# Dual_Motor_Driver.net
KiCad netlist of a schematic drawn in EAGLE
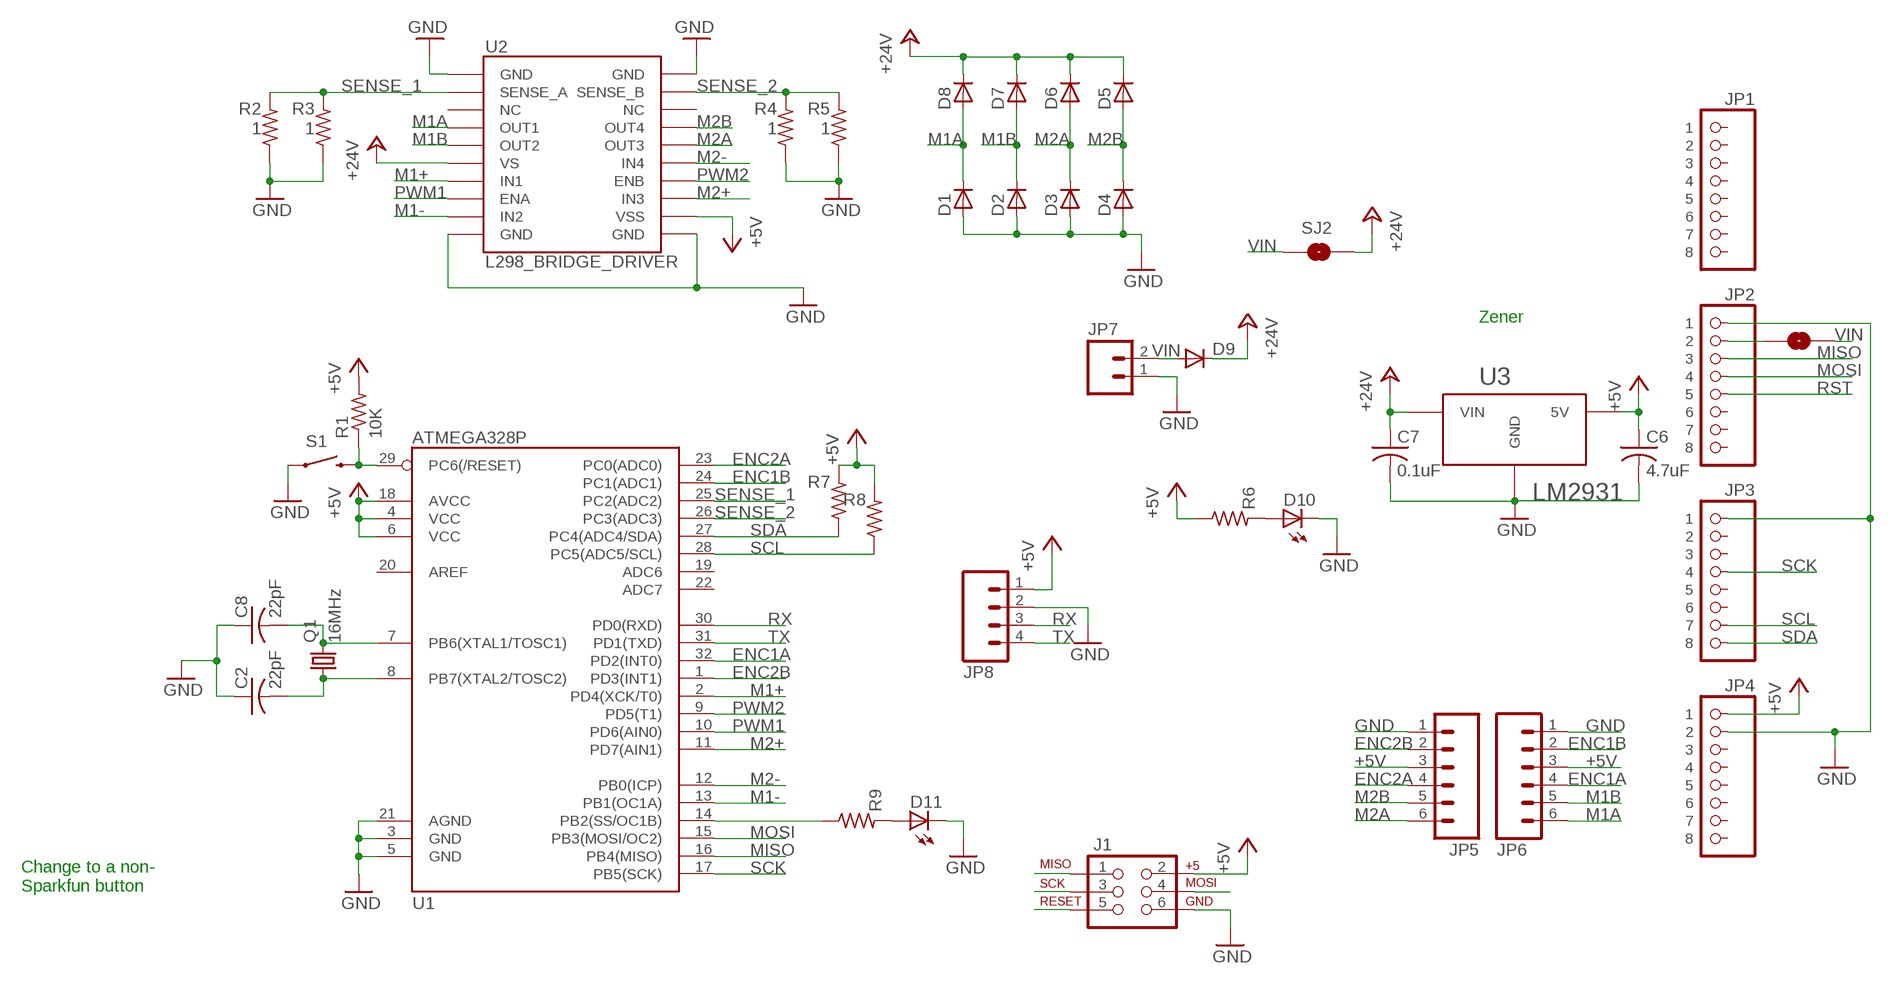
[diagram p0: schematic, sheet 1]

(export (version "E")
  (design (tool "Eeschema 10.0.6"))
  (components
    (comp (ref "C2")
      (value "22pF")
      (footprint "eagle-import:C0603")
      (libsource (lib "eagle-import") (part "C-USC0603"))
    )
    (comp (ref "C6")
      (value "4.7uF")
      (footprint "eagle-import:C0603")
      (libsource (lib "eagle-import") (part "C-USC0603"))
    )
    (comp (ref "C7")
      (value "0.1uF")
      (footprint "eagle-import:C0603")
      (libsource (lib "eagle-import") (part "C-USC0603"))
    )
    (comp (ref "C8")
      (value "22pF")
      (footprint "eagle-import:C0603")
      (libsource (lib "eagle-import") (part "C-USC0603"))
    )
    (comp (ref "D1")
      (value "D-SOD123")
      (footprint "eagle-import:SOD123")
      (fields (field (name "PART#") "CDBW140-G"))
      (libsource (lib "eagle-import") (part "D-SOD123"))
    )
    (comp (ref "D2")
      (value "D-SOD123")
      (footprint "eagle-import:SOD123")
      (fields (field (name "PART#") "CDBW140-G"))
      (libsource (lib "eagle-import") (part "D-SOD123"))
    )
    (comp (ref "D3")
      (value "D-SOD123")
      (footprint "eagle-import:SOD123")
      (fields (field (name "PART#") "CDBW140-G"))
      (libsource (lib "eagle-import") (part "D-SOD123"))
    )
    (comp (ref "D4")
      (value "D-SOD123")
      (footprint "eagle-import:SOD123")
      (fields (field (name "PART#") "CDBW140-G"))
      (libsource (lib "eagle-import") (part "D-SOD123"))
    )
    (comp (ref "D5")
      (value "D-SOD123")
      (footprint "eagle-import:SOD123")
      (fields (field (name "PART#") "CDBW140-G"))
      (libsource (lib "eagle-import") (part "D-SOD123"))
    )
    (comp (ref "D6")
      (value "D-SOD123")
      (footprint "eagle-import:SOD123")
      (fields (field (name "PART#") "CDBW140-G"))
      (libsource (lib "eagle-import") (part "D-SOD123"))
    )
    (comp (ref "D7")
      (value "D-SOD123")
      (footprint "eagle-import:SOD123")
      (fields (field (name "PART#") "CDBW140-G"))
      (libsource (lib "eagle-import") (part "D-SOD123"))
    )
    (comp (ref "D8")
      (value "D-SOD123")
      (footprint "eagle-import:SOD123")
      (fields (field (name "PART#") "CDBW140-G"))
      (libsource (lib "eagle-import") (part "D-SOD123"))
    )
    (comp (ref "D9")
      (value "DIODESMB")
      (footprint "eagle-import:SMB-DIODE")
      (libsource (lib "eagle-import") (part "DIODESMB"))
    )
    (comp (ref "D10")
      (value "LED-GREENLED-0805_NO_SILK")
      (footprint "eagle-import:LED-0805")
      (libsource (lib "eagle-import") (part "LED-GREENLED-0805_NO_SILK"))
    )
    (comp (ref "D11")
      (value "LED-GREENLED-0805_NO_SILK")
      (footprint "eagle-import:LED-0805")
      (libsource (lib "eagle-import") (part "LED-GREENLED-0805_NO_SILK"))
    )
    (comp (ref "J1")
      (value "AVR_SPI_PRG_62X3_LOCK")
      (footprint "eagle-import:2X3_LOCK")
      (libsource (lib "eagle-import") (part "AVR_SPI_PRG_62X3_LOCK"))
    )
    (comp (ref "JP1")
      (value "8-PIN_HEADER")
      (footprint "eagle-import:8-PIN_RECEPTACLE_LOCK_NO-SS")
      (libsource (lib "eagle-import") (part "8-PIN_HEADER"))
    )
    (comp (ref "JP2")
      (value "8-PIN_HEADER")
      (footprint "eagle-import:8-PIN_RECEPTACLE_LOCK_NO-SS")
      (libsource (lib "eagle-import") (part "8-PIN_HEADER"))
    )
    (comp (ref "JP3")
      (value "8-PIN_HEADER")
      (footprint "eagle-import:8-PIN_RECEPTACLE_LOCK_NO-SS")
      (libsource (lib "eagle-import") (part "8-PIN_HEADER"))
    )
    (comp (ref "JP4")
      (value "8-PIN_HEADER")
      (footprint "eagle-import:8-PIN_RECEPTACLE_LOCK_NO-SS")
      (libsource (lib "eagle-import") (part "8-PIN_HEADER"))
    )
    (comp (ref "JP5")
      (value "6-PIN-CONNECTORLEFT-MOTOR-JST")
      (footprint "eagle-import:MOTOR-JST-6-PTH-LEFT")
      (libsource (lib "eagle-import") (part "6-PIN-CONNECTORLEFT-MOTOR-JST"))
    )
    (comp (ref "JP6")
      (value "6-PIN-CONNECTORRIGHT-MOTOR-JST")
      (footprint "eagle-import:MOTOR-JST-6-PTH-RIGHT")
      (libsource (lib "eagle-import") (part "6-PIN-CONNECTORRIGHT-MOTOR-JST"))
    )
    (comp (ref "JP7")
      (value "M02PTH")
      (footprint "eagle-import:1X02")
      (libsource (lib "eagle-import") (part "M02PTH"))
    )
    (comp (ref "JP8")
      (value "M04LOCK")
      (footprint "eagle-import:1X04_LOCK")
      (libsource (lib "eagle-import") (part "M04LOCK"))
    )
    (comp (ref "Q1")
      (value "16MHz")
      (footprint "eagle-import:CTS406")
      (fields (field (name "PART#") "406C35D16M00000"))
      (libsource (lib "eagle-import") (part "CRYSTALCTS406"))
    )
    (comp (ref "R1")
      (value "10K")
      (footprint "eagle-import:R0603")
      (libsource (lib "eagle-import") (part "R-US_R0603"))
    )
    (comp (ref "R2")
      (value "1")
      (footprint "eagle-import:R0603")
      (libsource (lib "eagle-import") (part "R-US_R0603"))
    )
    (comp (ref "R3")
      (value "1")
      (footprint "eagle-import:R0603")
      (libsource (lib "eagle-import") (part "R-US_R0603"))
    )
    (comp (ref "R4")
      (value "1")
      (footprint "eagle-import:R0603")
      (libsource (lib "eagle-import") (part "R-US_R0603"))
    )
    (comp (ref "R5")
      (value "1")
      (footprint "eagle-import:R0603")
      (libsource (lib "eagle-import") (part "R-US_R0603"))
    )
    (comp (ref "R6")
      (value "R-US_R0603")
      (footprint "eagle-import:R0603")
      (libsource (lib "eagle-import") (part "R-US_R0603"))
    )
    (comp (ref "R7")
      (value "R-US_R0603")
      (footprint "eagle-import:R0603")
      (libsource (lib "eagle-import") (part "R-US_R0603"))
    )
    (comp (ref "R8")
      (value "R-US_R0603")
      (footprint "eagle-import:R0603")
      (libsource (lib "eagle-import") (part "R-US_R0603"))
    )
    (comp (ref "R9")
      (value "R-US_R0603")
      (footprint "eagle-import:R0603")
      (libsource (lib "eagle-import") (part "R-US_R0603"))
    )
    (comp (ref "S1")
      (value "SWITCH-MOMENTARY-2SMD")
      (footprint "eagle-import:TACTILE_SWITCH_SMD")
      (libsource (lib "eagle-import") (part "SWITCH-MOMENTARY-2SMD"))
    )
    (comp (ref "SJ1")
      (value "SOLDERJUMPERTRACE")
      (footprint "eagle-import:SJ_2S-TRACE")
      (libsource (lib "eagle-import") (part "SOLDERJUMPERTRACE"))
    )
    (comp (ref "SJ2")
      (value "SOLDERJUMPERNO")
      (footprint "eagle-import:SJ_2S-NO")
      (libsource (lib "eagle-import") (part "SOLDERJUMPERNO"))
    )
    (comp (ref "U1")
      (value "ATMEGA328P")
      (footprint "eagle-import:TQFP32-08")
      (libsource (lib "eagle-import") (part "ATMEGA328_SMT"))
    )
    (comp (ref "U2")
      (value "L298_BRIDGE_DRIVER")
      (footprint "eagle-import:POWERSO20")
      (libsource (lib "eagle-import") (part "L298_BRIDGE_DRIVER"))
    )
    (comp (ref "U3")
      (value "LM2931")
      (footprint "eagle-import:TO263")
      (libsource (lib "eagle-import") (part "LM2931"))
    )
  )
  (nets
    (net (code "1") (name "+5V") (class "Default")
      (node (ref "C6") (pin "1") (pinfunction "1_1") (pintype "passive"))
      (node (ref "J1") (pin "2") (pinfunction "2_2") (pintype "passive"))
      (node (ref "JP4") (pin "P$1") (pinfunction "1_P$1") (pintype "passive"))
      (node (ref "JP5") (pin "3") (pinfunction "3_3") (pintype "passive"))
      (node (ref "JP6") (pin "3") (pinfunction "3_3") (pintype "passive"))
      (node (ref "JP8") (pin "1") (pinfunction "1_1") (pintype "passive"))
      (node (ref "R1") (pin "2") (pinfunction "2_2") (pintype "passive"))
      (node (ref "R6") (pin "1") (pinfunction "1_1") (pintype "passive"))
      (node (ref "R7") (pin "2") (pinfunction "2_2") (pintype "passive"))
      (node (ref "R8") (pin "2") (pinfunction "2_2") (pintype "passive"))
      (node (ref "U1") (pin "18") (pinfunction "AVCC_18") (pintype "bidirectional"))
      (node (ref "U1") (pin "4") (pinfunction "VCC_4") (pintype "bidirectional"))
      (node (ref "U1") (pin "6") (pinfunction "VCC_6") (pintype "bidirectional"))
      (node (ref "U2") (pin "12") (pinfunction "VSS_12") (pintype "bidirectional"))
      (node (ref "U3") (pin "P$3") (pinfunction "5V_P$3") (pintype "bidirectional"))
    )
    (net (code "2") (name "+24V") (class "Default")
      (node (ref "C7") (pin "1") (pinfunction "1_1") (pintype "passive"))
      (node (ref "D5") (pin "1") (pinfunction "C_1") (pintype "passive"))
      (node (ref "D6") (pin "1") (pinfunction "C_1") (pintype "passive"))
      (node (ref "D7") (pin "1") (pinfunction "C_1") (pintype "passive"))
      (node (ref "D8") (pin "1") (pinfunction "C_1") (pintype "passive"))
      (node (ref "D9") (pin "C") (pinfunction "C_C") (pintype "passive"))
      (node (ref "SJ2") (pin "2") (pinfunction "2_2") (pintype "passive"))
      (node (ref "U2") (pin "6") (pinfunction "VS_6") (pintype "bidirectional"))
      (node (ref "U3") (pin "P$2") (pinfunction "VIN_P$2") (pintype "bidirectional"))
    )
    (net (code "3") (name "/ENC1A") (class "Default")
      (node (ref "JP6") (pin "4") (pinfunction "4_4") (pintype "passive"))
      (node (ref "U1") (pin "32") (pinfunction "PD2(INT0)_32") (pintype "bidirectional"))
    )
    (net (code "4") (name "/ENC1B") (class "Default")
      (node (ref "JP6") (pin "2") (pinfunction "2_2") (pintype "passive"))
      (node (ref "U1") (pin "24") (pinfunction "PC1(ADC1)_24") (pintype "bidirectional"))
    )
    (net (code "5") (name "/ENC2A") (class "Default")
      (node (ref "JP5") (pin "4") (pinfunction "4_4") (pintype "passive"))
      (node (ref "U1") (pin "23") (pinfunction "PC0(ADC0)_23") (pintype "bidirectional"))
    )
    (net (code "6") (name "/ENC2B") (class "Default")
      (node (ref "JP5") (pin "2") (pinfunction "2_2") (pintype "passive"))
      (node (ref "U1") (pin "1") (pinfunction "PD3(INT1)_1") (pintype "bidirectional"))
    )
    (net (code "7") (name "/M1+") (class "Default")
      (node (ref "U1") (pin "2") (pinfunction "PD4(XCK/T0)_2") (pintype "bidirectional"))
      (node (ref "U2") (pin "7") (pinfunction "IN1_7") (pintype "bidirectional"))
    )
    (net (code "8") (name "/M1-") (class "Default")
      (node (ref "U1") (pin "13") (pinfunction "PB1(OC1A)_13") (pintype "bidirectional"))
      (node (ref "U2") (pin "9") (pinfunction "IN2_9") (pintype "bidirectional"))
    )
    (net (code "9") (name "/M1A") (class "Default")
      (node (ref "D1") (pin "1") (pinfunction "C_1") (pintype "passive"))
      (node (ref "D8") (pin "2") (pinfunction "A_2") (pintype "passive"))
      (node (ref "JP6") (pin "6") (pinfunction "6_6") (pintype "passive"))
      (node (ref "U2") (pin "4") (pinfunction "OUT1_4") (pintype "bidirectional"))
    )
    (net (code "10") (name "/M1B") (class "Default")
      (node (ref "D2") (pin "1") (pinfunction "C_1") (pintype "passive"))
      (node (ref "D7") (pin "2") (pinfunction "A_2") (pintype "passive"))
      (node (ref "JP6") (pin "5") (pinfunction "5_5") (pintype "passive"))
      (node (ref "U2") (pin "5") (pinfunction "OUT2_5") (pintype "bidirectional"))
    )
    (net (code "11") (name "/M2+") (class "Default")
      (node (ref "U1") (pin "11") (pinfunction "PD7(AIN1)_11") (pintype "bidirectional"))
      (node (ref "U2") (pin "13") (pinfunction "IN3_13") (pintype "bidirectional"))
    )
    (net (code "12") (name "/M2-") (class "Default")
      (node (ref "U1") (pin "12") (pinfunction "PB0(ICP)_12") (pintype "bidirectional"))
      (node (ref "U2") (pin "15") (pinfunction "IN4_15") (pintype "bidirectional"))
    )
    (net (code "13") (name "/M2A") (class "Default")
      (node (ref "D3") (pin "1") (pinfunction "C_1") (pintype "passive"))
      (node (ref "D6") (pin "2") (pinfunction "A_2") (pintype "passive"))
      (node (ref "JP5") (pin "6") (pinfunction "6_6") (pintype "passive"))
      (node (ref "U2") (pin "16") (pinfunction "OUT3_16") (pintype "bidirectional"))
    )
    (net (code "14") (name "/M2B") (class "Default")
      (node (ref "D4") (pin "1") (pinfunction "C_1") (pintype "passive"))
      (node (ref "D5") (pin "2") (pinfunction "A_2") (pintype "passive"))
      (node (ref "JP5") (pin "5") (pinfunction "5_5") (pintype "passive"))
      (node (ref "U2") (pin "17") (pinfunction "OUT4_17") (pintype "bidirectional"))
    )
    (net (code "15") (name "/MISO") (class "Default")
      (node (ref "J1") (pin "1") (pinfunction "1_1") (pintype "passive"))
      (node (ref "JP2") (pin "P$3") (pinfunction "3_P$3") (pintype "passive"))
      (node (ref "U1") (pin "16") (pinfunction "PB4(MISO)_16") (pintype "bidirectional"))
    )
    (net (code "16") (name "/MOSI") (class "Default")
      (node (ref "J1") (pin "4") (pinfunction "4_4") (pintype "passive"))
      (node (ref "JP2") (pin "P$4") (pinfunction "4_P$4") (pintype "passive"))
      (node (ref "U1") (pin "15") (pinfunction "PB3(MOSI/OC2)_15") (pintype "bidirectional"))
    )
    (net (code "17") (name "/PWM1") (class "Default")
      (node (ref "U1") (pin "10") (pinfunction "PD6(AIN0)_10") (pintype "bidirectional"))
      (node (ref "U2") (pin "8") (pinfunction "ENA_8") (pintype "bidirectional"))
    )
    (net (code "18") (name "/PWM2") (class "Default")
      (node (ref "U1") (pin "9") (pinfunction "PD5(T1)_9") (pintype "bidirectional"))
      (node (ref "U2") (pin "14") (pinfunction "ENB_14") (pintype "bidirectional"))
    )
    (net (code "19") (name "/RESET") (class "Default")
      (node (ref "J1") (pin "5") (pinfunction "5_5") (pintype "passive"))
      (node (ref "R1") (pin "1") (pinfunction "1_1") (pintype "passive"))
      (node (ref "S1") (pin "3") (pinfunction "2_3") (pintype "passive"))
      (node (ref "U1") (pin "29") (pinfunction "PC6(/RESET)_29") (pintype "bidirectional"))
    )
    (net (code "20") (name "/RST") (class "Default")
      (node (ref "JP2") (pin "P$5") (pinfunction "5_P$5") (pintype "passive"))
    )
    (net (code "21") (name "/RX") (class "Default")
      (node (ref "JP8") (pin "3") (pinfunction "3_3") (pintype "passive"))
      (node (ref "U1") (pin "30") (pinfunction "PD0(RXD)_30") (pintype "bidirectional"))
    )
    (net (code "22") (name "/SCK") (class "Default")
      (node (ref "J1") (pin "3") (pinfunction "3_3") (pintype "passive"))
      (node (ref "JP3") (pin "P$4") (pinfunction "4_P$4") (pintype "passive"))
      (node (ref "U1") (pin "17") (pinfunction "PB5(SCK)_17") (pintype "bidirectional"))
    )
    (net (code "23") (name "/SCL") (class "Default")
      (node (ref "JP3") (pin "P$7") (pinfunction "7_P$7") (pintype "passive"))
      (node (ref "R8") (pin "1") (pinfunction "1_1") (pintype "passive"))
      (node (ref "U1") (pin "28") (pinfunction "PC5(ADC5/SCL)_28") (pintype "bidirectional"))
    )
    (net (code "24") (name "/SDA") (class "Default")
      (node (ref "JP3") (pin "P$8") (pinfunction "8_P$8") (pintype "passive"))
      (node (ref "R7") (pin "1") (pinfunction "1_1") (pintype "passive"))
      (node (ref "U1") (pin "27") (pinfunction "PC4(ADC4/SDA)_27") (pintype "bidirectional"))
    )
    (net (code "25") (name "/SENSE_1") (class "Default")
      (node (ref "R2") (pin "2") (pinfunction "2_2") (pintype "passive"))
      (node (ref "R3") (pin "2") (pinfunction "2_2") (pintype "passive"))
      (node (ref "U1") (pin "25") (pinfunction "PC2(ADC2)_25") (pintype "bidirectional"))
      (node (ref "U2") (pin "2") (pinfunction "SENSE_A_2") (pintype "bidirectional"))
    )
    (net (code "26") (name "/SENSE_2") (class "Default")
      (node (ref "R4") (pin "2") (pinfunction "2_2") (pintype "passive"))
      (node (ref "R5") (pin "2") (pinfunction "2_2") (pintype "passive"))
      (node (ref "U1") (pin "26") (pinfunction "PC3(ADC3)_26") (pintype "bidirectional"))
      (node (ref "U2") (pin "19") (pinfunction "SENSE_B_19") (pintype "bidirectional"))
    )
    (net (code "27") (name "/TX") (class "Default")
      (node (ref "JP8") (pin "4") (pinfunction "4_4") (pintype "passive"))
      (node (ref "U1") (pin "31") (pinfunction "PD1(TXD)_31") (pintype "bidirectional"))
    )
    (net (code "28") (name "/VIN") (class "Default")
      (node (ref "D9") (pin "A") (pinfunction "A_A") (pintype "passive"))
      (node (ref "JP7") (pin "2") (pinfunction "2_2") (pintype "passive"))
      (node (ref "SJ1") (pin "2") (pinfunction "2_2") (pintype "passive"))
      (node (ref "SJ2") (pin "1") (pinfunction "1_1") (pintype "passive"))
    )
    (net (code "29") (name "GND") (class "Default")
      (node (ref "C2") (pin "1") (pinfunction "1_1") (pintype "passive"))
      (node (ref "C6") (pin "2") (pinfunction "2_2") (pintype "passive"))
      (node (ref "C7") (pin "2") (pinfunction "2_2") (pintype "passive"))
      (node (ref "C8") (pin "1") (pinfunction "1_1") (pintype "passive"))
      (node (ref "D1") (pin "2") (pinfunction "A_2") (pintype "passive"))
      (node (ref "D10") (pin "2") (pinfunction "C_2") (pintype "passive"))
      (node (ref "D11") (pin "2") (pinfunction "C_2") (pintype "passive"))
      (node (ref "D2") (pin "2") (pinfunction "A_2") (pintype "passive"))
      (node (ref "D3") (pin "2") (pinfunction "A_2") (pintype "passive"))
      (node (ref "D4") (pin "2") (pinfunction "A_2") (pintype "passive"))
      (node (ref "J1") (pin "6") (pinfunction "6_6") (pintype "passive"))
      (node (ref "JP2") (pin "P$1") (pinfunction "1_P$1") (pintype "passive"))
      (node (ref "JP3") (pin "P$1") (pinfunction "1_P$1") (pintype "passive"))
      (node (ref "JP4") (pin "P$2") (pinfunction "2_P$2") (pintype "passive"))
      (node (ref "JP5") (pin "1") (pinfunction "1_1") (pintype "passive"))
      (node (ref "JP6") (pin "1") (pinfunction "1_1") (pintype "passive"))
      (node (ref "JP7") (pin "1") (pinfunction "1_1") (pintype "passive"))
      (node (ref "JP8") (pin "2") (pinfunction "2_2") (pintype "passive"))
      (node (ref "R2") (pin "1") (pinfunction "1_1") (pintype "passive"))
      (node (ref "R3") (pin "1") (pinfunction "1_1") (pintype "passive"))
      (node (ref "R4") (pin "1") (pinfunction "1_1") (pintype "passive"))
      (node (ref "R5") (pin "1") (pinfunction "1_1") (pintype "passive"))
      (node (ref "S1") (pin "1") (pinfunction "1_1") (pintype "passive"))
      (node (ref "U1") (pin "21") (pinfunction "AGND_21") (pintype "bidirectional"))
      (node (ref "U1") (pin "3") (pinfunction "GND_3") (pintype "bidirectional"))
      (node (ref "U1") (pin "5") (pinfunction "GND_5") (pintype "bidirectional"))
      (node (ref "U2") (pin "1") (pinfunction "GND_1") (pintype "bidirectional"))
      (node (ref "U2") (pin "10") (pinfunction "GND_10") (pintype "bidirectional"))
      (node (ref "U2") (pin "11") (pinfunction "GND_11") (pintype "bidirectional"))
      (node (ref "U2") (pin "20") (pinfunction "GND_20") (pintype "bidirectional"))
      (node (ref "U3") (pin "P$1") (pinfunction "GND_P$1") (pintype "bidirectional"))
    )
    (net (code "30") (name "Net-(D10-A)") (class "Default")
      (node (ref "D10") (pin "1") (pinfunction "A_1") (pintype "passive"))
      (node (ref "R6") (pin "2") (pinfunction "2_2") (pintype "passive"))
    )
    (net (code "31") (name "Net-(D11-A)") (class "Default")
      (node (ref "D11") (pin "1") (pinfunction "A_1") (pintype "passive"))
      (node (ref "R9") (pin "2") (pinfunction "2_2") (pintype "passive"))
    )
    (net (code "32") (name "Net-(JP2-2)") (class "Default")
      (node (ref "JP2") (pin "P$2") (pinfunction "2_P$2") (pintype "passive"))
      (node (ref "SJ1") (pin "1") (pinfunction "1_1") (pintype "passive"))
    )
    (net (code "33") (name "Net-(Q1-2)") (class "Default")
      (node (ref "C8") (pin "2") (pinfunction "2_2") (pintype "passive"))
      (node (ref "Q1") (pin "3") (pinfunction "2_3") (pintype "passive"))
      (node (ref "U1") (pin "7") (pinfunction "PB6(XTAL1/TOSC1)_7") (pintype "bidirectional"))
    )
    (net (code "34") (name "Net-(U1-PB2(SS{slash}OC1B))") (class "Default")
      (node (ref "R9") (pin "1") (pinfunction "1_1") (pintype "passive"))
      (node (ref "U1") (pin "14") (pinfunction "PB2(SS/OC1B)_14") (pintype "bidirectional"))
    )
    (net (code "35") (name "Net-(U1-PB7(XTAL2{slash}TOSC2))") (class "Default")
      (node (ref "C2") (pin "2") (pinfunction "2_2") (pintype "passive"))
      (node (ref "Q1") (pin "1") (pinfunction "1_1") (pintype "passive"))
      (node (ref "U1") (pin "8") (pinfunction "PB7(XTAL2/TOSC2)_8") (pintype "bidirectional"))
    )
    (net (code "36") (name "unconnected-(JP1-1-PadP$1)") (class "Default")
      (node (ref "JP1") (pin "P$1") (pinfunction "1_P$1") (pintype "passive"))
    )
    (net (code "37") (name "unconnected-(JP1-2-PadP$2)") (class "Default")
      (node (ref "JP1") (pin "P$2") (pinfunction "2_P$2") (pintype "passive"))
    )
    (net (code "38") (name "unconnected-(JP1-3-PadP$3)") (class "Default")
      (node (ref "JP1") (pin "P$3") (pinfunction "3_P$3") (pintype "passive"))
    )
    (net (code "39") (name "unconnected-(JP1-4-PadP$4)") (class "Default")
      (node (ref "JP1") (pin "P$4") (pinfunction "4_P$4") (pintype "passive"))
    )
    (net (code "40") (name "unconnected-(JP1-5-PadP$5)") (class "Default")
      (node (ref "JP1") (pin "P$5") (pinfunction "5_P$5") (pintype "passive"))
    )
    (net (code "41") (name "unconnected-(JP1-6-PadP$6)") (class "Default")
      (node (ref "JP1") (pin "P$6") (pinfunction "6_P$6") (pintype "passive"))
    )
    (net (code "42") (name "unconnected-(JP1-7-PadP$7)") (class "Default")
      (node (ref "JP1") (pin "P$7") (pinfunction "7_P$7") (pintype "passive"))
    )
    (net (code "43") (name "unconnected-(JP1-8-PadP$8)") (class "Default")
      (node (ref "JP1") (pin "P$8") (pinfunction "8_P$8") (pintype "passive"))
    )
    (net (code "44") (name "unconnected-(JP2-6-PadP$6)") (class "Default")
      (node (ref "JP2") (pin "P$6") (pinfunction "6_P$6") (pintype "passive"))
    )
    (net (code "45") (name "unconnected-(JP2-7-PadP$7)") (class "Default")
      (node (ref "JP2") (pin "P$7") (pinfunction "7_P$7") (pintype "passive"))
    )
    (net (code "46") (name "unconnected-(JP2-8-PadP$8)") (class "Default")
      (node (ref "JP2") (pin "P$8") (pinfunction "8_P$8") (pintype "passive"))
    )
    (net (code "47") (name "unconnected-(JP3-2-PadP$2)") (class "Default")
      (node (ref "JP3") (pin "P$2") (pinfunction "2_P$2") (pintype "passive"))
    )
    (net (code "48") (name "unconnected-(JP3-3-PadP$3)") (class "Default")
      (node (ref "JP3") (pin "P$3") (pinfunction "3_P$3") (pintype "passive"))
    )
    (net (code "49") (name "unconnected-(JP3-5-PadP$5)") (class "Default")
      (node (ref "JP3") (pin "P$5") (pinfunction "5_P$5") (pintype "passive"))
    )
    (net (code "50") (name "unconnected-(JP3-6-PadP$6)") (class "Default")
      (node (ref "JP3") (pin "P$6") (pinfunction "6_P$6") (pintype "passive"))
    )
    (net (code "51") (name "unconnected-(JP4-3-PadP$3)") (class "Default")
      (node (ref "JP4") (pin "P$3") (pinfunction "3_P$3") (pintype "passive"))
    )
    (net (code "52") (name "unconnected-(JP4-4-PadP$4)") (class "Default")
      (node (ref "JP4") (pin "P$4") (pinfunction "4_P$4") (pintype "passive"))
    )
    (net (code "53") (name "unconnected-(JP4-5-PadP$5)") (class "Default")
      (node (ref "JP4") (pin "P$5") (pinfunction "5_P$5") (pintype "passive"))
    )
    (net (code "54") (name "unconnected-(JP4-6-PadP$6)") (class "Default")
      (node (ref "JP4") (pin "P$6") (pinfunction "6_P$6") (pintype "passive"))
    )
    (net (code "55") (name "unconnected-(JP4-7-PadP$7)") (class "Default")
      (node (ref "JP4") (pin "P$7") (pinfunction "7_P$7") (pintype "passive"))
    )
    (net (code "56") (name "unconnected-(JP4-8-PadP$8)") (class "Default")
      (node (ref "JP4") (pin "P$8") (pinfunction "8_P$8") (pintype "passive"))
    )
    (net (code "57") (name "unconnected-(U1-ADC6-Pad19)") (class "Default")
      (node (ref "U1") (pin "19") (pinfunction "ADC6_19") (pintype "bidirectional"))
    )
    (net (code "58") (name "unconnected-(U1-ADC7-Pad22)") (class "Default")
      (node (ref "U1") (pin "22") (pinfunction "ADC7_22") (pintype "bidirectional"))
    )
    (net (code "59") (name "unconnected-(U1-AREF-Pad20)") (class "Default")
      (node (ref "U1") (pin "20") (pinfunction "AREF_20") (pintype "bidirectional"))
    )
    (net (code "60") (name "unconnected-(U2-NC-Pad3)") (class "Default")
      (node (ref "U2") (pin "3") (pinfunction "NC_3") (pintype "bidirectional"))
    )
    (net (code "61") (name "unconnected-(U2-NC-Pad18)") (class "Default")
      (node (ref "U2") (pin "18") (pinfunction "NC_18") (pintype "bidirectional"))
    )
  )
)
